# 1_P1_schdoc.net
KiCad netlist of a schematic drawn in Altium Designer
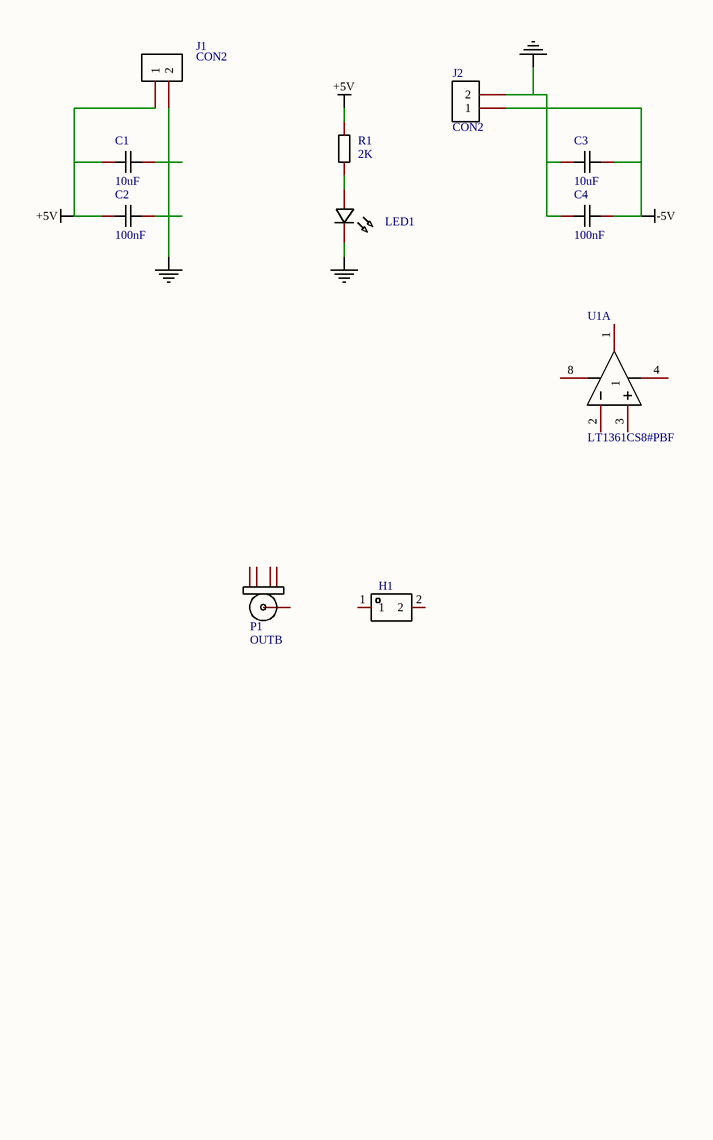
[diagram p0: 1_P1.schdoc.schdoc]

(export (version "E")
  (design (tool "Eeschema 10.0.6"))
  (components
    (comp (ref "C1")
      (value "10uF")
      (fields (field (name "NAME") "10uF"))
      (libsource (lib "altium-import") (part "root_0_CAP_0805_"))
    )
    (comp (ref "C2")
      (value "100nF")
      (fields (field (name "NAME") "100nF"))
      (libsource (lib "altium-import") (part "root_0_CAP_0805_"))
    )
    (comp (ref "C3")
      (value "10uF")
      (fields (field (name "NAME") "10uF"))
      (libsource (lib "altium-import") (part "root_0_CAP_0805_"))
    )
    (comp (ref "C4")
      (value "100nF")
      (fields (field (name "NAME") "100nF"))
      (libsource (lib "altium-import") (part "root_0_CAP_0805_"))
    )
    (comp (ref "H1")
      (value "HDR-M_2.54_2x1")
      (libsource (lib "altium-import") (part "root_0_HDR-M_2.54_2x1_"))
    )
    (comp (ref "J1")
      (value "CON2")
      (fields (field (name "NAME") "CON2"))
      (libsource (lib "altium-import") (part "root_0_CON2_"))
    )
    (comp (ref "J2")
      (value "CON2")
      (fields (field (name "NAME") "CON2"))
      (libsource (lib "altium-import") (part "root_1_CON2_"))
    )
    (comp (ref "LED1") (value "LED_0805-R") (libsource (lib "altium-import") (part "root_3_LED_0805-R_")))
    (comp (ref "P1")
      (value "OUTB")
      (fields (field (name "NAME") "OUTB"))
      (libsource (lib "altium-import") (part "root_2_BNC_"))
    )
    (comp (ref "R1")
      (value "2K")
      (fields (field (name "NAME") "2K"))
      (libsource (lib "altium-import") (part "root_3_Res_0805_"))
    )
    (comp (ref "U1")
      (value "LT1361CS8#PBF")
      (description "放大器数:双路;增益带宽积(GBP):50MHz;输入偏置电流(Ib):300nA;压摆率(SR):800V/us;带宽(-3db):-;")
      (fields (field (name "NAME") "LT1361CS8#PBF") (field (name "MANUFACTURER") "ADI(亚德诺)"))
      (libsource (lib "altium-import") (part "root_1_LT1361CS8#PBF_"))
    )
  )
  (nets
    (net (code "1") (name "+5V") (class "Default")
      (node (ref "C1") (pin "1") (pinfunction "1_1") (pintype "passive"))
      (node (ref "C2") (pin "1") (pinfunction "1_1") (pintype "passive"))
      (node (ref "J1") (pin "1") (pinfunction "1_1") (pintype "passive"))
      (node (ref "R1") (pin "1") (pinfunction "1_1") (pintype "passive"))
    )
    (net (code "2") (name "-5V") (class "Default")
      (node (ref "C3") (pin "2") (pinfunction "2_2") (pintype "passive"))
      (node (ref "C4") (pin "2") (pinfunction "2_2") (pintype "passive"))
      (node (ref "J2") (pin "1") (pinfunction "1_1") (pintype "passive"))
    )
    (net (code "3") (name "GND") (class "Default")
      (node (ref "C1") (pin "2") (pinfunction "2_2") (pintype "passive"))
      (node (ref "C2") (pin "2") (pinfunction "2_2") (pintype "passive"))
      (node (ref "C3") (pin "1") (pinfunction "1_1") (pintype "passive"))
      (node (ref "C4") (pin "1") (pinfunction "1_1") (pintype "passive"))
      (node (ref "J1") (pin "2") (pinfunction "2_2") (pintype "passive"))
      (node (ref "J2") (pin "2") (pinfunction "2_2") (pintype "passive"))
      (node (ref "LED1") (pin "1") (pinfunction "C_1") (pintype "passive"))
    )
    (net (code "4") (name "Net-(LED1-A)") (class "Default")
      (node (ref "LED1") (pin "2") (pinfunction "A_2") (pintype "passive"))
      (node (ref "R1") (pin "2") (pinfunction "2_2") (pintype "passive"))
    )
    (net (code "5") (name "unconnected-(H1-Pad1)") (class "Default")
      (node (ref "H1") (pin "1") (pinfunction "1_1") (pintype "passive"))
    )
    (net (code "6") (name "unconnected-(H1-Pad2)") (class "Default")
      (node (ref "H1") (pin "2") (pinfunction "2_2") (pintype "passive"))
    )
    (net (code "7") (name "unconnected-(P1-GND-Pad2)") (class "Default")
      (node (ref "P1") (pin "2") (pinfunction "GND_2") (pintype "passive"))
    )
    (net (code "8") (name "unconnected-(P1-GND-Pad3)") (class "Default")
      (node (ref "P1") (pin "3") (pinfunction "GND_3") (pintype "passive"))
    )
    (net (code "9") (name "unconnected-(P1-GND-Pad4)") (class "Default")
      (node (ref "P1") (pin "4") (pinfunction "GND_4") (pintype "passive"))
    )
    (net (code "10") (name "unconnected-(P1-GND-Pad5)") (class "Default")
      (node (ref "P1") (pin "5") (pinfunction "GND_5") (pintype "passive"))
    )
    (net (code "11") (name "unconnected-(P1-X-Pad1)") (class "Default")
      (node (ref "P1") (pin "1") (pinfunction "X_1") (pintype "passive"))
    )
    (net (code "12") (name "unconnected-(U1A-INA+-Pad3)") (class "Default")
      (node (ref "U1") (pin "3") (pinfunction "INA+_3") (pintype "passive"))
    )
    (net (code "13") (name "unconnected-(U1A-INA--Pad2)") (class "Default")
      (node (ref "U1") (pin "2") (pinfunction "INA-_2") (pintype "passive"))
    )
    (net (code "14") (name "unconnected-(U1A-OUTA-Pad1)") (class "Default")
      (node (ref "U1") (pin "1") (pinfunction "OUTA_1") (pintype "passive"))
    )
    (net (code "15") (name "unconnected-(U1A-V+-Pad8)") (class "Default")
      (node (ref "U1") (pin "8") (pinfunction "V+_8") (pintype "passive"))
    )
    (net (code "16") (name "unconnected-(U1A-V--Pad4)") (class "Default")
      (node (ref "U1") (pin "4") (pinfunction "V-_4") (pintype "passive"))
    )
  )
)
